# FeatherProto-RJ45-V4_0.net
KiCad netlist of a schematic drawn in EAGLE
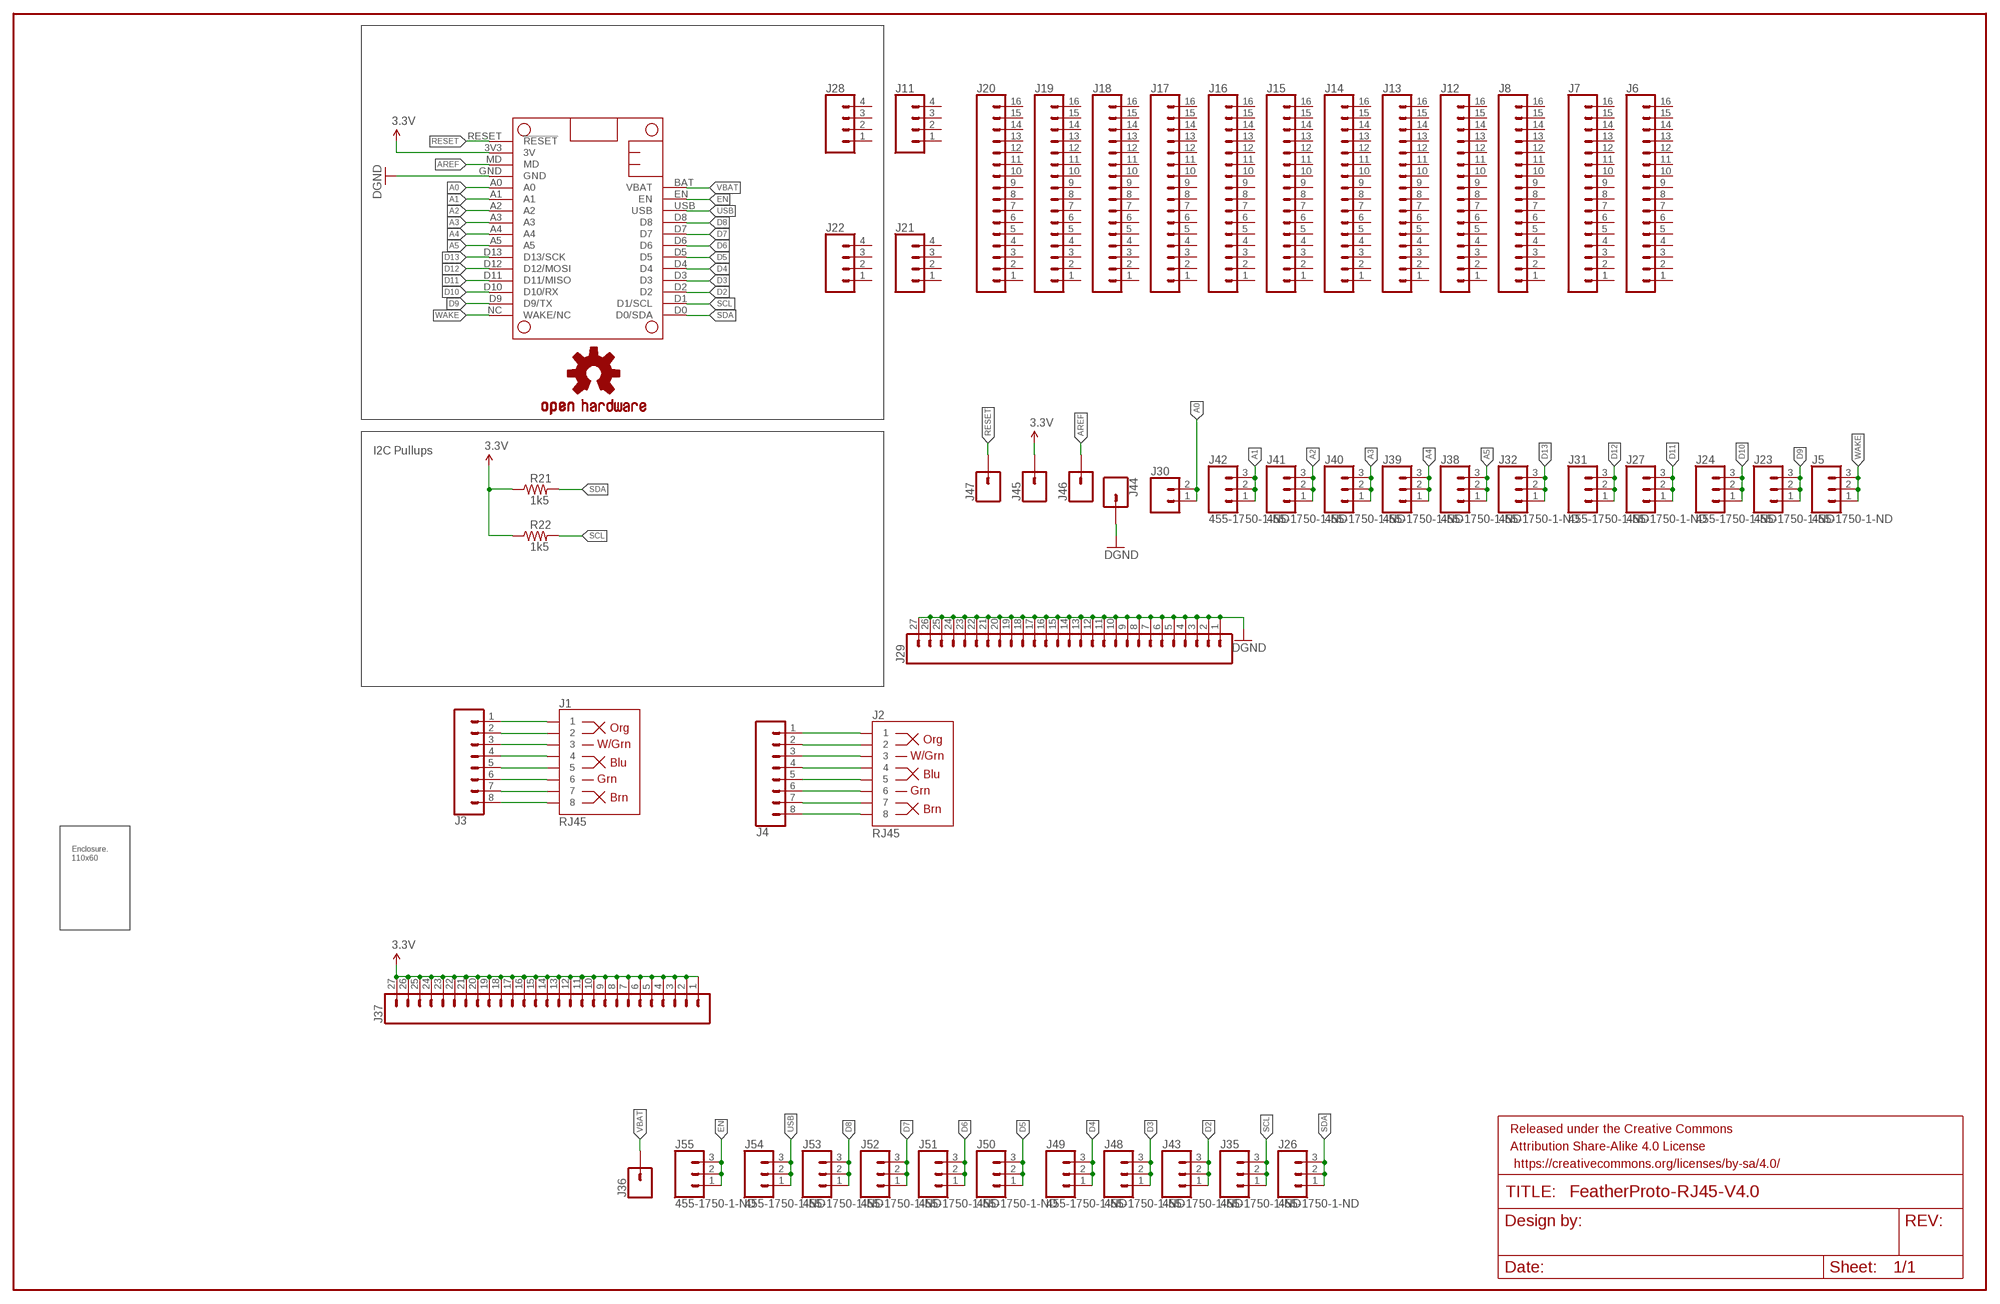
[diagram p0: schematic, sheet 1]

(export (version "E")
  (design (tool "Eeschema 10.0.6"))
  (components
    (comp (ref "FRAME2")
      (value "FRAME-LEDGER")
      (footprint "eagle-import:CREATIVE_COMMONS")
      (libsource (lib "eagle-import") (part "FRAME-LEDGER"))
    )
    (comp (ref "J1")
      (value "RJ45")
      (footprint "eagle-import:RJ45-8")
      (libsource (lib "eagle-import") (part "RJ45-8"))
    )
    (comp (ref "J2")
      (value "RJ45")
      (footprint "eagle-import:RJ45-8")
      (libsource (lib "eagle-import") (part "RJ45-8"))
    )
    (comp (ref "J3")
      (value "CONN_08\"")
      (footprint "eagle-import:1X08")
      (libsource (lib "eagle-import") (part "CONN_08{dblquote}"))
    )
    (comp (ref "J4")
      (value "CONN_08\"")
      (footprint "eagle-import:1X08")
      (libsource (lib "eagle-import") (part "CONN_08{dblquote}"))
    )
    (comp (ref "J5")
      (value "455-1750-1-ND")
      (footprint "eagle-import:1X03")
      (libsource (lib "eagle-import") (part "CONN_03"))
    )
    (comp (ref "J6")
      (value "CONN_161X16_NO_SILK")
      (footprint "eagle-import:1X16_NO_SILK")
      (libsource (lib "eagle-import") (part "CONN_161X16_NO_SILK"))
    )
    (comp (ref "J7")
      (value "CONN_161X16_NO_SILK")
      (footprint "eagle-import:1X16_NO_SILK")
      (libsource (lib "eagle-import") (part "CONN_161X16_NO_SILK"))
    )
    (comp (ref "J8")
      (value "CONN_161X16_NO_SILK")
      (footprint "eagle-import:1X16_NO_SILK")
      (libsource (lib "eagle-import") (part "CONN_161X16_NO_SILK"))
    )
    (comp (ref "J11")
      (value "CONN_041X04_NO_SILK")
      (footprint "eagle-import:1X04_NO_SILK")
      (libsource (lib "eagle-import") (part "CONN_041X04_NO_SILK"))
    )
    (comp (ref "J12")
      (value "CONN_161X16_NO_SILK")
      (footprint "eagle-import:1X16_NO_SILK")
      (libsource (lib "eagle-import") (part "CONN_161X16_NO_SILK"))
    )
    (comp (ref "J13")
      (value "CONN_161X16_NO_SILK")
      (footprint "eagle-import:1X16_NO_SILK")
      (libsource (lib "eagle-import") (part "CONN_161X16_NO_SILK"))
    )
    (comp (ref "J14")
      (value "CONN_161X16_NO_SILK")
      (footprint "eagle-import:1X16_NO_SILK")
      (libsource (lib "eagle-import") (part "CONN_161X16_NO_SILK"))
    )
    (comp (ref "J15")
      (value "CONN_161X16_NO_SILK")
      (footprint "eagle-import:1X16_NO_SILK")
      (libsource (lib "eagle-import") (part "CONN_161X16_NO_SILK"))
    )
    (comp (ref "J16")
      (value "CONN_161X16_NO_SILK")
      (footprint "eagle-import:1X16_NO_SILK")
      (libsource (lib "eagle-import") (part "CONN_161X16_NO_SILK"))
    )
    (comp (ref "J17")
      (value "CONN_161X16_NO_SILK")
      (footprint "eagle-import:1X16_NO_SILK")
      (libsource (lib "eagle-import") (part "CONN_161X16_NO_SILK"))
    )
    (comp (ref "J18")
      (value "CONN_161X16_NO_SILK")
      (footprint "eagle-import:1X16_NO_SILK")
      (libsource (lib "eagle-import") (part "CONN_161X16_NO_SILK"))
    )
    (comp (ref "J19")
      (value "CONN_161X16_NO_SILK")
      (footprint "eagle-import:1X16_NO_SILK")
      (libsource (lib "eagle-import") (part "CONN_161X16_NO_SILK"))
    )
    (comp (ref "J20")
      (value "CONN_161X16_NO_SILK")
      (footprint "eagle-import:1X16_NO_SILK")
      (libsource (lib "eagle-import") (part "CONN_161X16_NO_SILK"))
    )
    (comp (ref "J21")
      (value "CONN_041X04_NO_SILK")
      (footprint "eagle-import:1X04_NO_SILK")
      (libsource (lib "eagle-import") (part "CONN_041X04_NO_SILK"))
    )
    (comp (ref "J22")
      (value "CONN_041X04_NO_SILK")
      (footprint "eagle-import:1X04_NO_SILK")
      (libsource (lib "eagle-import") (part "CONN_041X04_NO_SILK"))
    )
    (comp (ref "J23")
      (value "455-1750-1-ND")
      (footprint "eagle-import:1X03")
      (libsource (lib "eagle-import") (part "CONN_03"))
    )
    (comp (ref "J24")
      (value "455-1750-1-ND")
      (footprint "eagle-import:1X03")
      (libsource (lib "eagle-import") (part "CONN_03"))
    )
    (comp (ref "J26")
      (value "455-1750-1-ND")
      (footprint "eagle-import:1X03")
      (libsource (lib "eagle-import") (part "CONN_03"))
    )
    (comp (ref "J27")
      (value "455-1750-1-ND")
      (footprint "eagle-import:1X03")
      (libsource (lib "eagle-import") (part "CONN_03"))
    )
    (comp (ref "J28")
      (value "CONN_041X04_NO_SILK")
      (footprint "eagle-import:1X04_NO_SILK")
      (libsource (lib "eagle-import") (part "CONN_041X04_NO_SILK"))
    )
    (comp (ref "J29")
      (value "CONN_27")
      (footprint "eagle-import:1X27")
      (libsource (lib "eagle-import") (part "CONN_27"))
    )
    (comp (ref "J30")
      (value "CONN_02")
      (footprint "eagle-import:1X02")
      (libsource (lib "eagle-import") (part "CONN_02"))
    )
    (comp (ref "J31")
      (value "455-1750-1-ND")
      (footprint "eagle-import:1X03")
      (libsource (lib "eagle-import") (part "CONN_03"))
    )
    (comp (ref "J32")
      (value "455-1750-1-ND")
      (footprint "eagle-import:1X03")
      (libsource (lib "eagle-import") (part "CONN_03"))
    )
    (comp (ref "J35")
      (value "455-1750-1-ND")
      (footprint "eagle-import:1X03")
      (libsource (lib "eagle-import") (part "CONN_03"))
    )
    (comp (ref "J36")
      (value "CONN_01PTH_NO_SILK_YES_STOP")
      (footprint "eagle-import:1X01_NO_SILK")
      (libsource (lib "eagle-import") (part "CONN_01PTH_NO_SILK_YES_STOP"))
    )
    (comp (ref "J37")
      (value "CONN_27")
      (footprint "eagle-import:1X27")
      (libsource (lib "eagle-import") (part "CONN_27"))
    )
    (comp (ref "J38")
      (value "455-1750-1-ND")
      (footprint "eagle-import:1X03")
      (libsource (lib "eagle-import") (part "CONN_03"))
    )
    (comp (ref "J39")
      (value "455-1750-1-ND")
      (footprint "eagle-import:1X03")
      (libsource (lib "eagle-import") (part "CONN_03"))
    )
    (comp (ref "J40")
      (value "455-1750-1-ND")
      (footprint "eagle-import:1X03")
      (libsource (lib "eagle-import") (part "CONN_03"))
    )
    (comp (ref "J41")
      (value "455-1750-1-ND")
      (footprint "eagle-import:1X03")
      (libsource (lib "eagle-import") (part "CONN_03"))
    )
    (comp (ref "J42")
      (value "455-1750-1-ND")
      (footprint "eagle-import:1X03")
      (libsource (lib "eagle-import") (part "CONN_03"))
    )
    (comp (ref "J43")
      (value "455-1750-1-ND")
      (footprint "eagle-import:1X03")
      (libsource (lib "eagle-import") (part "CONN_03"))
    )
    (comp (ref "J44")
      (value "CONN_01PTH_NO_SILK_YES_STOP")
      (footprint "eagle-import:1X01_NO_SILK")
      (libsource (lib "eagle-import") (part "CONN_01PTH_NO_SILK_YES_STOP"))
    )
    (comp (ref "J45")
      (value "CONN_01PTH_NO_SILK_YES_STOP")
      (footprint "eagle-import:1X01_NO_SILK")
      (libsource (lib "eagle-import") (part "CONN_01PTH_NO_SILK_YES_STOP"))
    )
    (comp (ref "J46")
      (value "CONN_01PTH_NO_SILK_YES_STOP")
      (footprint "eagle-import:1X01_NO_SILK")
      (libsource (lib "eagle-import") (part "CONN_01PTH_NO_SILK_YES_STOP"))
    )
    (comp (ref "J47")
      (value "CONN_01PTH_NO_SILK_YES_STOP")
      (footprint "eagle-import:1X01_NO_SILK")
      (libsource (lib "eagle-import") (part "CONN_01PTH_NO_SILK_YES_STOP"))
    )
    (comp (ref "J48")
      (value "455-1750-1-ND")
      (footprint "eagle-import:1X03")
      (libsource (lib "eagle-import") (part "CONN_03"))
    )
    (comp (ref "J49")
      (value "455-1750-1-ND")
      (footprint "eagle-import:1X03")
      (libsource (lib "eagle-import") (part "CONN_03"))
    )
    (comp (ref "J50")
      (value "455-1750-1-ND")
      (footprint "eagle-import:1X03")
      (libsource (lib "eagle-import") (part "CONN_03"))
    )
    (comp (ref "J51")
      (value "455-1750-1-ND")
      (footprint "eagle-import:1X03")
      (libsource (lib "eagle-import") (part "CONN_03"))
    )
    (comp (ref "J52")
      (value "455-1750-1-ND")
      (footprint "eagle-import:1X03")
      (libsource (lib "eagle-import") (part "CONN_03"))
    )
    (comp (ref "J53")
      (value "455-1750-1-ND")
      (footprint "eagle-import:1X03")
      (libsource (lib "eagle-import") (part "CONN_03"))
    )
    (comp (ref "J54")
      (value "455-1750-1-ND")
      (footprint "eagle-import:1X03")
      (libsource (lib "eagle-import") (part "CONN_03"))
    )
    (comp (ref "J55")
      (value "455-1750-1-ND")
      (footprint "eagle-import:1X03")
      (libsource (lib "eagle-import") (part "CONN_03"))
    )
    (comp (ref "LOGO1")
      (value "OSHW-LOGOM")
      (footprint "eagle-import:OSHW-LOGO-M")
      (libsource (lib "eagle-import") (part "OSHW-LOGOM"))
    )
    (comp (ref "MS1")
      (value "XENONA")
      (footprint "eagle-import:XENON_BREAKOUT_A")
      (libsource (lib "eagle-import") (part "XENONA"))
    )
    (comp (ref "R21")
      (value "1k5")
      (footprint "eagle-import:0805")
      (libsource (lib "eagle-import") (part "RESISTOR0805"))
    )
    (comp (ref "R22")
      (value "1k5")
      (footprint "eagle-import:0805")
      (libsource (lib "eagle-import") (part "RESISTOR0805"))
    )
    (comp (ref "U$1")
      (value "CAMDENBOSS-ENCLOSURE-110X60MAX")
      (footprint "eagle-import:CAMDENBOSS_ENCLOSRE_110X60_WIDE_EXTENDED_3")
      (libsource (lib "eagle-import") (part "CAMDENBOSS-ENCLOSURE-110X60MAX"))
    )
  )
  (nets
    (net (code "1") (name "3.3V") (class "Default")
      (node (ref "J37") (pin "1") (pinfunction "1_1") (pintype "passive"))
      (node (ref "J37") (pin "10") (pinfunction "10_10") (pintype "passive"))
      (node (ref "J37") (pin "11") (pinfunction "11_11") (pintype "passive"))
      (node (ref "J37") (pin "12") (pinfunction "12_12") (pintype "passive"))
      (node (ref "J37") (pin "13") (pinfunction "13_13") (pintype "passive"))
      (node (ref "J37") (pin "14") (pinfunction "14_14") (pintype "passive"))
      (node (ref "J37") (pin "15") (pinfunction "15_15") (pintype "passive"))
      (node (ref "J37") (pin "16") (pinfunction "16_16") (pintype "passive"))
      (node (ref "J37") (pin "17") (pinfunction "17_17") (pintype "passive"))
      (node (ref "J37") (pin "18") (pinfunction "18_18") (pintype "passive"))
      (node (ref "J37") (pin "19") (pinfunction "19_19") (pintype "passive"))
      (node (ref "J37") (pin "2") (pinfunction "2_2") (pintype "passive"))
      (node (ref "J37") (pin "20") (pinfunction "20_20") (pintype "passive"))
      (node (ref "J37") (pin "21") (pinfunction "21_21") (pintype "passive"))
      (node (ref "J37") (pin "22") (pinfunction "22_22") (pintype "passive"))
      (node (ref "J37") (pin "23") (pinfunction "23_23") (pintype "passive"))
      (node (ref "J37") (pin "24") (pinfunction "24_24") (pintype "passive"))
      (node (ref "J37") (pin "25") (pinfunction "25_25") (pintype "passive"))
      (node (ref "J37") (pin "26") (pinfunction "26_26") (pintype "passive"))
      (node (ref "J37") (pin "27") (pinfunction "27_27") (pintype "passive"))
      (node (ref "J37") (pin "3") (pinfunction "3_3") (pintype "passive"))
      (node (ref "J37") (pin "4") (pinfunction "4_4") (pintype "passive"))
      (node (ref "J37") (pin "5") (pinfunction "5_5") (pintype "passive"))
      (node (ref "J37") (pin "6") (pinfunction "6_6") (pintype "passive"))
      (node (ref "J37") (pin "7") (pinfunction "7_7") (pintype "passive"))
      (node (ref "J37") (pin "8") (pinfunction "8_8") (pintype "passive"))
      (node (ref "J37") (pin "9") (pinfunction "9_9") (pintype "passive"))
      (node (ref "J45") (pin "1") (pinfunction "1_1") (pintype "passive"))
      (node (ref "MS1") (pin "3V3") (pinfunction "3V_3V3") (pintype "power_in"))
      (node (ref "R21") (pin "1") (pinfunction "1_1") (pintype "passive"))
      (node (ref "R22") (pin "1") (pinfunction "1_1") (pintype "passive"))
    )
    (net (code "2") (name "A0") (class "Default")
      (node (ref "J30") (pin "1") (pinfunction "1_1") (pintype "passive"))
      (node (ref "J30") (pin "2") (pinfunction "2_2") (pintype "passive"))
      (node (ref "MS1") (pin "A0") (pinfunction "A0_A0") (pintype "bidirectional"))
    )
    (net (code "3") (name "A1") (class "Default")
      (node (ref "J42") (pin "1") (pinfunction "1_1") (pintype "passive"))
      (node (ref "J42") (pin "2") (pinfunction "2_2") (pintype "passive"))
      (node (ref "J42") (pin "3") (pinfunction "3_3") (pintype "passive"))
      (node (ref "MS1") (pin "A1") (pinfunction "A1_A1") (pintype "bidirectional"))
    )
    (net (code "4") (name "A2") (class "Default")
      (node (ref "J41") (pin "1") (pinfunction "1_1") (pintype "passive"))
      (node (ref "J41") (pin "2") (pinfunction "2_2") (pintype "passive"))
      (node (ref "J41") (pin "3") (pinfunction "3_3") (pintype "passive"))
      (node (ref "MS1") (pin "A2") (pinfunction "A2_A2") (pintype "bidirectional"))
    )
    (net (code "5") (name "A3") (class "Default")
      (node (ref "J40") (pin "1") (pinfunction "1_1") (pintype "passive"))
      (node (ref "J40") (pin "2") (pinfunction "2_2") (pintype "passive"))
      (node (ref "J40") (pin "3") (pinfunction "3_3") (pintype "passive"))
      (node (ref "MS1") (pin "A3") (pinfunction "A3_A3") (pintype "bidirectional"))
    )
    (net (code "6") (name "A4") (class "Default")
      (node (ref "J39") (pin "1") (pinfunction "1_1") (pintype "passive"))
      (node (ref "J39") (pin "2") (pinfunction "2_2") (pintype "passive"))
      (node (ref "J39") (pin "3") (pinfunction "3_3") (pintype "passive"))
      (node (ref "MS1") (pin "A4") (pinfunction "A4_A4") (pintype "bidirectional"))
    )
    (net (code "7") (name "A5") (class "Default")
      (node (ref "J38") (pin "1") (pinfunction "1_1") (pintype "passive"))
      (node (ref "J38") (pin "2") (pinfunction "2_2") (pintype "passive"))
      (node (ref "J38") (pin "3") (pinfunction "3_3") (pintype "passive"))
      (node (ref "MS1") (pin "A5") (pinfunction "A5_A5") (pintype "bidirectional"))
    )
    (net (code "8") (name "AREF") (class "Default")
      (node (ref "J46") (pin "1") (pinfunction "1_1") (pintype "passive"))
      (node (ref "MS1") (pin "MD") (pinfunction "MD_MD") (pintype "passive"))
    )
    (net (code "9") (name "D2") (class "Default")
      (node (ref "J43") (pin "1") (pinfunction "1_1") (pintype "passive"))
      (node (ref "J43") (pin "2") (pinfunction "2_2") (pintype "passive"))
      (node (ref "J43") (pin "3") (pinfunction "3_3") (pintype "passive"))
      (node (ref "MS1") (pin "D2") (pinfunction "D2_D2") (pintype "bidirectional"))
    )
    (net (code "10") (name "D3") (class "Default")
      (node (ref "J48") (pin "1") (pinfunction "1_1") (pintype "passive"))
      (node (ref "J48") (pin "2") (pinfunction "2_2") (pintype "passive"))
      (node (ref "J48") (pin "3") (pinfunction "3_3") (pintype "passive"))
      (node (ref "MS1") (pin "D3") (pinfunction "D3_D3") (pintype "bidirectional"))
    )
    (net (code "11") (name "D4") (class "Default")
      (node (ref "J49") (pin "1") (pinfunction "1_1") (pintype "passive"))
      (node (ref "J49") (pin "2") (pinfunction "2_2") (pintype "passive"))
      (node (ref "J49") (pin "3") (pinfunction "3_3") (pintype "passive"))
      (node (ref "MS1") (pin "D4") (pinfunction "D4_D4") (pintype "bidirectional"))
    )
    (net (code "12") (name "D5") (class "Default")
      (node (ref "J50") (pin "1") (pinfunction "1_1") (pintype "passive"))
      (node (ref "J50") (pin "2") (pinfunction "2_2") (pintype "passive"))
      (node (ref "J50") (pin "3") (pinfunction "3_3") (pintype "passive"))
      (node (ref "MS1") (pin "D5") (pinfunction "D5_D5") (pintype "bidirectional"))
    )
    (net (code "13") (name "D6") (class "Default")
      (node (ref "J51") (pin "1") (pinfunction "1_1") (pintype "passive"))
      (node (ref "J51") (pin "2") (pinfunction "2_2") (pintype "passive"))
      (node (ref "J51") (pin "3") (pinfunction "3_3") (pintype "passive"))
      (node (ref "MS1") (pin "D6") (pinfunction "D6_D6") (pintype "bidirectional"))
    )
    (net (code "14") (name "D7") (class "Default")
      (node (ref "J52") (pin "1") (pinfunction "1_1") (pintype "passive"))
      (node (ref "J52") (pin "2") (pinfunction "2_2") (pintype "passive"))
      (node (ref "J52") (pin "3") (pinfunction "3_3") (pintype "passive"))
      (node (ref "MS1") (pin "D7") (pinfunction "D7_D7") (pintype "bidirectional"))
    )
    (net (code "15") (name "D8") (class "Default")
      (node (ref "J53") (pin "1") (pinfunction "1_1") (pintype "passive"))
      (node (ref "J53") (pin "2") (pinfunction "2_2") (pintype "passive"))
      (node (ref "J53") (pin "3") (pinfunction "3_3") (pintype "passive"))
      (node (ref "MS1") (pin "D8") (pinfunction "D8_D8") (pintype "bidirectional"))
    )
    (net (code "16") (name "D9") (class "Default")
      (node (ref "J23") (pin "1") (pinfunction "1_1") (pintype "passive"))
      (node (ref "J23") (pin "2") (pinfunction "2_2") (pintype "passive"))
      (node (ref "J23") (pin "3") (pinfunction "3_3") (pintype "passive"))
      (node (ref "MS1") (pin "D9") (pinfunction "D9/TX_D9") (pintype "bidirectional"))
    )
    (net (code "17") (name "D10") (class "Default")
      (node (ref "J24") (pin "1") (pinfunction "1_1") (pintype "passive"))
      (node (ref "J24") (pin "2") (pinfunction "2_2") (pintype "passive"))
      (node (ref "J24") (pin "3") (pinfunction "3_3") (pintype "passive"))
      (node (ref "MS1") (pin "D10") (pinfunction "D10/RX_D10") (pintype "bidirectional"))
    )
    (net (code "18") (name "D11") (class "Default")
      (node (ref "J27") (pin "1") (pinfunction "1_1") (pintype "passive"))
      (node (ref "J27") (pin "2") (pinfunction "2_2") (pintype "passive"))
      (node (ref "J27") (pin "3") (pinfunction "3_3") (pintype "passive"))
      (node (ref "MS1") (pin "D11") (pinfunction "D11/MISO_D11") (pintype "bidirectional"))
    )
    (net (code "19") (name "D12") (class "Default")
      (node (ref "J31") (pin "1") (pinfunction "1_1") (pintype "passive"))
      (node (ref "J31") (pin "2") (pinfunction "2_2") (pintype "passive"))
      (node (ref "J31") (pin "3") (pinfunction "3_3") (pintype "passive"))
      (node (ref "MS1") (pin "D12") (pinfunction "D12/MOSI_D12") (pintype "bidirectional"))
    )
    (net (code "20") (name "D13") (class "Default")
      (node (ref "J32") (pin "1") (pinfunction "1_1") (pintype "passive"))
      (node (ref "J32") (pin "2") (pinfunction "2_2") (pintype "passive"))
      (node (ref "J32") (pin "3") (pinfunction "3_3") (pintype "passive"))
      (node (ref "MS1") (pin "D13") (pinfunction "D13/SCK_D13") (pintype "bidirectional"))
    )
    (net (code "21") (name "DGND") (class "Default")
      (node (ref "J29") (pin "1") (pinfunction "1_1") (pintype "passive"))
      (node (ref "J29") (pin "10") (pinfunction "10_10") (pintype "passive"))
      (node (ref "J29") (pin "11") (pinfunction "11_11") (pintype "passive"))
      (node (ref "J29") (pin "12") (pinfunction "12_12") (pintype "passive"))
      (node (ref "J29") (pin "13") (pinfunction "13_13") (pintype "passive"))
      (node (ref "J29") (pin "14") (pinfunction "14_14") (pintype "passive"))
      (node (ref "J29") (pin "15") (pinfunction "15_15") (pintype "passive"))
      (node (ref "J29") (pin "16") (pinfunction "16_16") (pintype "passive"))
      (node (ref "J29") (pin "17") (pinfunction "17_17") (pintype "passive"))
      (node (ref "J29") (pin "18") (pinfunction "18_18") (pintype "passive"))
      (node (ref "J29") (pin "19") (pinfunction "19_19") (pintype "passive"))
      (node (ref "J29") (pin "2") (pinfunction "2_2") (pintype "passive"))
      (node (ref "J29") (pin "20") (pinfunction "20_20") (pintype "passive"))
      (node (ref "J29") (pin "21") (pinfunction "21_21") (pintype "passive"))
      (node (ref "J29") (pin "22") (pinfunction "22_22") (pintype "passive"))
      (node (ref "J29") (pin "23") (pinfunction "23_23") (pintype "passive"))
      (node (ref "J29") (pin "24") (pinfunction "24_24") (pintype "passive"))
      (node (ref "J29") (pin "25") (pinfunction "25_25") (pintype "passive"))
      (node (ref "J29") (pin "26") (pinfunction "26_26") (pintype "passive"))
      (node (ref "J29") (pin "27") (pinfunction "27_27") (pintype "passive"))
      (node (ref "J29") (pin "3") (pinfunction "3_3") (pintype "passive"))
      (node (ref "J29") (pin "4") (pinfunction "4_4") (pintype "passive"))
      (node (ref "J29") (pin "5") (pinfunction "5_5") (pintype "passive"))
      (node (ref "J29") (pin "6") (pinfunction "6_6") (pintype "passive"))
      (node (ref "J29") (pin "7") (pinfunction "7_7") (pintype "passive"))
      (node (ref "J29") (pin "8") (pinfunction "8_8") (pintype "passive"))
      (node (ref "J29") (pin "9") (pinfunction "9_9") (pintype "passive"))
      (node (ref "J44") (pin "1") (pinfunction "1_1") (pintype "passive"))
      (node (ref "MS1") (pin "GND") (pinfunction "GND_GND") (pintype "power_in"))
    )
    (net (code "22") (name "EN") (class "Default")
      (node (ref "J55") (pin "1") (pinfunction "1_1") (pintype "passive"))
      (node (ref "J55") (pin "2") (pinfunction "2_2") (pintype "passive"))
      (node (ref "J55") (pin "3") (pinfunction "3_3") (pintype "passive"))
      (node (ref "MS1") (pin "EN") (pinfunction "EN_EN") (pintype "passive"))
    )
    (net (code "23") (name "Net-(J1-Pad1)") (class "Default")
      (node (ref "J1") (pin "1") (pinfunction "1_1") (pintype "bidirectional"))
      (node (ref "J3") (pin "1") (pinfunction "1_1") (pintype "passive"))
    )
    (net (code "24") (name "Net-(J1-Pad2)") (class "Default")
      (node (ref "J1") (pin "2") (pinfunction "2_2") (pintype "bidirectional"))
      (node (ref "J3") (pin "2") (pinfunction "2_2") (pintype "passive"))
    )
    (net (code "25") (name "Net-(J1-Pad3)") (class "Default")
      (node (ref "J1") (pin "3") (pinfunction "3_3") (pintype "bidirectional"))
      (node (ref "J3") (pin "3") (pinfunction "3_3") (pintype "passive"))
    )
    (net (code "26") (name "Net-(J1-Pad4)") (class "Default")
      (node (ref "J1") (pin "4") (pinfunction "4_4") (pintype "bidirectional"))
      (node (ref "J3") (pin "4") (pinfunction "4_4") (pintype "passive"))
    )
    (net (code "27") (name "Net-(J1-Pad5)") (class "Default")
      (node (ref "J1") (pin "5") (pinfunction "5_5") (pintype "bidirectional"))
      (node (ref "J3") (pin "5") (pinfunction "5_5") (pintype "passive"))
    )
    (net (code "28") (name "Net-(J1-Pad6)") (class "Default")
      (node (ref "J1") (pin "6") (pinfunction "6_6") (pintype "bidirectional"))
      (node (ref "J3") (pin "6") (pinfunction "6_6") (pintype "passive"))
    )
    (net (code "29") (name "Net-(J1-Pad7)") (class "Default")
      (node (ref "J1") (pin "7") (pinfunction "7_7") (pintype "bidirectional"))
      (node (ref "J3") (pin "7") (pinfunction "7_7") (pintype "passive"))
    )
    (net (code "30") (name "Net-(J1-Pad8)") (class "Default")
      (node (ref "J1") (pin "8") (pinfunction "8_8") (pintype "bidirectional"))
      (node (ref "J3") (pin "8") (pinfunction "8_8") (pintype "passive"))
    )
    (net (code "31") (name "Net-(J2-Pad1)") (class "Default")
      (node (ref "J2") (pin "1") (pinfunction "1_1") (pintype "bidirectional"))
      (node (ref "J4") (pin "1") (pinfunction "1_1") (pintype "passive"))
    )
    (net (code "32") (name "Net-(J2-Pad2)") (class "Default")
      (node (ref "J2") (pin "2") (pinfunction "2_2") (pintype "bidirectional"))
      (node (ref "J4") (pin "2") (pinfunction "2_2") (pintype "passive"))
    )
    (net (code "33") (name "Net-(J2-Pad3)") (class "Default")
      (node (ref "J2") (pin "3") (pinfunction "3_3") (pintype "bidirectional"))
      (node (ref "J4") (pin "3") (pinfunction "3_3") (pintype "passive"))
    )
    (net (code "34") (name "Net-(J2-Pad4)") (class "Default")
      (node (ref "J2") (pin "4") (pinfunction "4_4") (pintype "bidirectional"))
      (node (ref "J4") (pin "4") (pinfunction "4_4") (pintype "passive"))
    )
    (net (code "35") (name "Net-(J2-Pad5)") (class "Default")
      (node (ref "J2") (pin "5") (pinfunction "5_5") (pintype "bidirectional"))
      (node (ref "J4") (pin "5") (pinfunction "5_5") (pintype "passive"))
    )
    (net (code "36") (name "Net-(J2-Pad6)") (class "Default")
      (node (ref "J2") (pin "6") (pinfunction "6_6") (pintype "bidirectional"))
      (node (ref "J4") (pin "6") (pinfunction "6_6") (pintype "passive"))
    )
    (net (code "37") (name "Net-(J2-Pad7)") (class "Default")
      (node (ref "J2") (pin "7") (pinfunction "7_7") (pintype "bidirectional"))
      (node (ref "J4") (pin "7") (pinfunction "7_7") (pintype "passive"))
    )
    (net (code "38") (name "Net-(J2-Pad8)") (class "Default")
      (node (ref "J2") (pin "8") (pinfunction "8_8") (pintype "bidirectional"))
      (node (ref "J4") (pin "8") (pinfunction "8_8") (pintype "passive"))
    )
    (net (code "39") (name "RESET") (class "Default")
      (node (ref "J47") (pin "1") (pinfunction "1_1") (pintype "passive"))
      (node (ref "MS1") (pin "RESET") (pinfunction "~{RESET}_RESET") (pintype "input"))
    )
    (net (code "40") (name "SCL") (class "Default")
      (node (ref "J35") (pin "1") (pinfunction "1_1") (pintype "passive"))
      (node (ref "J35") (pin "2") (pinfunction "2_2") (pintype "passive"))
      (node (ref "J35") (pin "3") (pinfunction "3_3") (pintype "passive"))
      (node (ref "MS1") (pin "D1") (pinfunction "D1/SCL_D1") (pintype "bidirectional"))
      (node (ref "R22") (pin "2") (pinfunction "2_2") (pintype "passive"))
    )
    (net (code "41") (name "SDA") (class "Default")
      (node (ref "J26") (pin "1") (pinfunction "1_1") (pintype "passive"))
      (node (ref "J26") (pin "2") (pinfunction "2_2") (pintype "passive"))
      (node (ref "J26") (pin "3") (pinfunction "3_3") (pintype "passive"))
      (node (ref "MS1") (pin "D0") (pinfunction "D0/SDA_D0") (pintype "bidirectional"))
      (node (ref "R21") (pin "2") (pinfunction "2_2") (pintype "passive"))
    )
    (net (code "42") (name "USB") (class "Default")
      (node (ref "J54") (pin "1") (pinfunction "1_1") (pintype "passive"))
      (node (ref "J54") (pin "2") (pinfunction "2_2") (pintype "passive"))
      (node (ref "J54") (pin "3") (pinfunction "3_3") (pintype "passive"))
      (node (ref "MS1") (pin "USB") (pinfunction "USB_USB") (pintype "power_in"))
    )
    (net (code "43") (name "VBAT") (class "Default")
      (node (ref "J36") (pin "1") (pinfunction "1_1") (pintype "passive"))
      (node (ref "MS1") (pin "BAT") (pinfunction "VBAT_BAT") (pintype "power_in"))
    )
    (net (code "44") (name "WAKE") (class "Default")
      (node (ref "J5") (pin "1") (pinfunction "1_1") (pintype "passive"))
      (node (ref "J5") (pin "2") (pinfunction "2_2") (pintype "passive"))
      (node (ref "J5") (pin "3") (pinfunction "3_3") (pintype "passive"))
      (node (ref "MS1") (pin "NC") (pinfunction "WAKE/NC_NC") (pintype "passive"))
    )
    (net (code "45") (name "unconnected-(J6-Pad1)") (class "Default")
      (node (ref "J6") (pin "1") (pinfunction "1_1") (pintype "passive"))
    )
    (net (code "46") (name "unconnected-(J6-Pad2)") (class "Default")
      (node (ref "J6") (pin "2") (pinfunction "2_2") (pintype "passive"))
    )
    (net (code "47") (name "unconnected-(J6-Pad3)") (class "Default")
      (node (ref "J6") (pin "3") (pinfunction "3_3") (pintype "passive"))
    )
    (net (code "48") (name "unconnected-(J6-Pad4)") (class "Default")
      (node (ref "J6") (pin "4") (pinfunction "4_4") (pintype "passive"))
    )
    (net (code "49") (name "unconnected-(J6-Pad5)") (class "Default")
      (node (ref "J6") (pin "5") (pinfunction "5_5") (pintype "passive"))
    )
    (net (code "50") (name "unconnected-(J6-Pad6)") (class "Default")
      (node (ref "J6") (pin "6") (pinfunction "6_6") (pintype "passive"))
    )
    (net (code "51") (name "unconnected-(J6-Pad7)") (class "Default")
      (node (ref "J6") (pin "7") (pinfunction "7_7") (pintype "passive"))
    )
    (net (code "52") (name "unconnected-(J6-Pad8)") (class "Default")
      (node (ref "J6") (pin "8") (pinfunction "8_8") (pintype "passive"))
    )
    (net (code "53") (name "unconnected-(J6-Pad9)") (class "Default")
      (node (ref "J6") (pin "9") (pinfunction "9_9") (pintype "passive"))
    )
    (net (code "54") (name "unconnected-(J6-Pad10)") (class "Default")
      (node (ref "J6") (pin "10") (pinfunction "10_10") (pintype "passive"))
    )
    (net (code "55") (name "unconnected-(J6-Pad11)") (class "Default")
      (node (ref "J6") (pin "11") (pinfunction "11_11") (pintype "passive"))
    )
    (net (code "56") (name "unconnected-(J6-Pad12)") (class "Default")
      (node (ref "J6") (pin "12") (pinfunction "12_12") (pintype "passive"))
    )
    (net (code "57") (name "unconnected-(J6-Pad13)") (class "Default")
      (node (ref "J6") (pin "13") (pinfunction "13_13") (pintype "passive"))
    )
    (net (code "58") (name "unconnected-(J6-Pad14)") (class "Default")
      (node (ref "J6") (pin "14") (pinfunction "14_14") (pintype "passive"))
    )
    (net (code "59") (name "unconnected-(J6-Pad15)") (class "Default")
      (node (ref "J6") (pin "15") (pinfunction "15_15") (pintype "passive"))
    )
    (net (code "60") (name "unconnected-(J6-Pad16)") (class "Default")
      (node (ref "J6") (pin "16") (pinfunction "16_16") (pintype "passive"))
    )
    (net (code "61") (name "unconnected-(J7-Pad1)") (class "Default")
      (node (ref "J7") (pin "1") (pinfunction "1_1") (pintype "passive"))
    )
    (net (code "62") (name "unconnected-(J7-Pad2)") (class "Default")
      (node (ref "J7") (pin "2") (pinfunction "2_2") (pintype "passive"))
    )
    (net (code "63") (name "unconnected-(J7-Pad3)") (class "Default")
      (node (ref "J7") (pin "3") (pinfunction "3_3") (pintype "passive"))
    )
    (net (code "64") (name "unconnected-(J7-Pad4)") (class "Default")
      (node (ref "J7") (pin "4") (pinfunction "4_4") (pintype "passive"))
    )
    (net (code "65") (name "unconnected-(J7-Pad5)") (class "Default")
      (node (ref "J7") (pin "5") (pinfunction "5_5") (pintype "passive"))
    )
    (net (code "66") (name "unconnected-(J7-Pad6)") (class "Default")
      (node (ref "J7") (pin "6") (pinfunction "6_6") (pintype "passive"))
    )
    (net (code "67") (name "unconnected-(J7-Pad7)") (class "Default")
      (node (ref "J7") (pin "7") (pinfunction "7_7") (pintype "passive"))
    )
    (net (code "68") (name "unconnected-(J7-Pad8)") (class "Default")
      (node (ref "J7") (pin "8") (pinfunction "8_8") (pintype "passive"))
    )
    (net (code "69") (name "unconnected-(J7-Pad9)") (class "Default")
      (node (ref "J7") (pin "9") (pinfunction "9_9") (pintype "passive"))
    )
    (net (code "70") (name "unconnected-(J7-Pad10)") (class "Default")
      (node (ref "J7") (pin "10") (pinfunction "10_10") (pintype "passive"))
    )
    (net (code "71") (name "unconnected-(J7-Pad11)") (class "Default")
      (node (ref "J7") (pin "11") (pinfunction "11_11") (pintype "passive"))
    )
    (net (code "72") (name "unconnected-(J7-Pad12)") (class "Default")
      (node (ref "J7") (pin "12") (pinfunction "12_12") (pintype "passive"))
    )
    (net (code "73") (name "unconnected-(J7-Pad13)") (class "Default")
      (node (ref "J7") (pin "13") (pinfunction "13_13") (pintype "passive"))
    )
    (net (code "74") (name "unconnected-(J7-Pad14)") (class "Default")
      (node (ref "J7") (pin "14") (pinfunction "14_14") (pintype "passive"))
    )
    (net (code "75") (name "unconnected-(J7-Pad15)") (class "Default")
      (node (ref "J7") (pin "15") (pinfunction "15_15") (pintype "passive"))
    )
    (net (code "76") (name "unconnected-(J7-Pad16)") (class "Default")
      (node (ref "J7") (pin "16") (pinfunction "16_16") (pintype "passive"))
    )
    (net (code "77") (name "unconnected-(J8-Pad1)") (class "Default")
      (node (ref "J8") (pin "1") (pinfunction "1_1") (pintype "passive"))
    )
    (net (code "78") (name "unconnected-(J8-Pad2)") (class "Default")
      (node (ref "J8") (pin "2") (pinfunction "2_2") (pintype "passive"))
    )
    (net (code "79") (name "unconnected-(J8-Pad3)") (class "Default")
      (node (ref "J8") (pin "3") (pinfunction "3_3") (pintype "passive"))
    )
    (net (code "80") (name "unconnected-(J8-Pad4)") (class "Default")
      (node (ref "J8") (pin "4") (pinfunction "4_4") (pintype "passive"))
    )
    (net (code "81") (name "unconnected-(J8-Pad5)") (class "Default")
      (node (ref "J8") (pin "5") (pinfunction "5_5") (pintype "passive"))
    )
    (net (code "82") (name "unconnected-(J8-Pad6)") (class "Default")
      (node (ref "J8") (pin "6") (pinfunction "6_6") (pintype "passive"))
    )
    (net (code "83") (name "unconnected-(J8-Pad7)") (class "Default")
      (node (ref "J8") (pin "7") (pinfunction "7_7") (pintype "passive"))
    )
    (net (code "84") (name "unconnected-(J8-Pad8)") (class "Default")
      (node (ref "J8") (pin "8") (pinfunction "8_8") (pintype "passive"))
    )
    (net (code "85") (name "unconnected-(J8-Pad9)") (class "Default")
      (node (ref "J8") (pin "9") (pinfunction "9_9") (pintype "passive"))
    )
    (net (code "86") (name "unconnected-(J8-Pad10)") (class "Default")
      (node (ref "J8") (pin "10") (pinfunction "10_10") (pintype "passive"))
    )
    (net (code "87") (name "unconnected-(J8-Pad11)") (class "Default")
      (node (ref "J8") (pin "11") (pinfunction "11_11") (pintype "passive"))
    )
    (net (code "88") (name "unconnected-(J8-Pad12)") (class "Default")
      (node (ref "J8") (pin "12") (pinfunction "12_12") (pintype "passive"))
    )
    (net (code "89") (name "unconnected-(J8-Pad13)") (class "Default")
      (node (ref "J8") (pin "13") (pinfunction "13_13") (pintype "passive"))
    )
    (net (code "90") (name "unconnected-(J8-Pad14)") (class "Default")
      (node (ref "J8") (pin "14") (pinfunction "14_14") (pintype "passive"))
    )
    (net (code "91") (name "unconnected-(J8-Pad15)") (class "Default")
      (node (ref "J8") (pin "15") (pinfunction "15_15") (pintype "passive"))
    )
    (net (code "92") (name "unconnected-(J8-Pad16)") (class "Default")
      (node (ref "J8") (pin "16") (pinfunction "16_16") (pintype "passive"))
    )
    (net (code "93") (name "unconnected-(J11-Pad1)") (class "Default")
      (node (ref "J11") (pin "1") (pinfunction "1_1") (pintype "passive"))
    )
    (net (code "94") (name "unconnected-(J11-Pad2)") (class "Default")
      (node (ref "J11") (pin "2") (pinfunction "2_2") (pintype "passive"))
    )
    (net (code "95") (name "unconnected-(J11-Pad3)") (class "Default")
      (node (ref "J11") (pin "3") (pinfunction "3_3") (pintype "passive"))
    )
    (net (code "96") (name "unconnected-(J11-Pad4)") (class "Default")
      (node (ref "J11") (pin "4") (pinfunction "4_4") (pintype "passive"))
    )
    (net (code "97") (name "unconnected-(J12-Pad1)") (class "Default")
      (node (ref "J12") (pin "1") (pinfunction "1_1") (pintype "passive"))
    )
    (net (code "98") (name "unconnected-(J12-Pad2)") (class "Default")
      (node (ref "J12") (pin "2") (pinfunction "2_2") (pintype "passive"))
    )
    (net (code "99") (name "unconnected-(J12-Pad3)") (class "Default")
      (node (ref "J12") (pin "3") (pinfunction "3_3") (pintype "passive"))
    )
    (net (code "100") (name "unconnected-(J12-Pad4)") (class "Default")
      (node (ref "J12") (pin "4") (pinfunction "4_4") (pintype "passive"))
    )
    (net (code "101") (name "unconnected-(J12-Pad5)") (class "Default")
      (node (ref "J12") (pin "5") (pinfunction "5_5") (pintype "passive"))
    )
    (net (code "102") (name "unconnected-(J12-Pad6)") (class "Default")
      (node (ref "J12") (pin "6") (pinfunction "6_6") (pintype "passive"))
    )
    (net (code "103") (name "unconnected-(J12-Pad7)") (class "Default")
      (node (ref "J12") (pin "7") (pinfunction "7_7") (pintype "passive"))
    )
    (net (code "104") (name "unconnected-(J12-Pad8)") (class "Default")
      (node (ref "J12") (pin "8") (pinfunction "8_8") (pintype "passive"))
    )
    (net (code "105") (name "unconnected-(J12-Pad9)") (class "Default")
      (node (ref "J12") (pin "9") (pinfunction "9_9") (pintype "passive"))
    )
    (net (code "106") (name "unconnected-(J12-Pad10)") (class "Default")
      (node (ref "J12") (pin "10") (pinfunction "10_10") (pintype "passive"))
    )
    (net (code "107") (name "unconnected-(J12-Pad11)") (class "Default")
      (node (ref "J12") (pin "11") (pinfunction "11_11") (pintype "passive"))
    )
    (net (code "108") (name "unconnected-(J12-Pad12)") (class "Default")
      (node (ref "J12") (pin "12") (pinfunction "12_12") (pintype "passive"))
    )
    (net (code "109") (name "unconnected-(J12-Pad13)") (class "Default")
      (node (ref "J12") (pin "13") (pinfunction "13_13") (pintype "passive"))
    )
    (net (code "110") (name "unconnected-(J12-Pad14)") (class "Default")
      (node (ref "J12") (pin "14") (pinfunction "14_14") (pintype "passive"))
    )
    (net (code "111") (name "unconnected-(J12-Pad15)") (class "Default")
      (node (ref "J12") (pin "15") (pinfunction "15_15") (pintype "passive"))
    )
    (net (code "112") (name "unconnected-(J12-Pad16)") (class "Default")
      (node (ref "J12") (pin "16") (pinfunction "16_16") (pintype "passive"))
    )
    (net (code "113") (name "unconnected-(J13-Pad1)") (class "Default")
      (node (ref "J13") (pin "1") (pinfunction "1_1") (pintype "passive"))
    )
    (net (code "114") (name "unconnected-(J13-Pad2)") (class "Default")
      (node (ref "J13") (pin "2") (pinfunction "2_2") (pintype "passive"))
    )
    (net (code "115") (name "unconnected-(J13-Pad3)") (class "Default")
      (node (ref "J13") (pin "3") (pinfunction "3_3") (pintype "passive"))
    )
    (net (code "116") (name "unconnected-(J13-Pad4)") (class "Default")
      (node (ref "J13") (pin "4") (pinfunction "4_4") (pintype "passive"))
    )
    (net (code "117") (name "unconnected-(J13-Pad5)") (class "Default")
      (node (ref "J13") (pin "5") (pinfunction "5_5") (pintype "passive"))
    )
    (net (code "118") (name "unconnected-(J13-Pad6)") (class "Default")
      (node (ref "J13") (pin "6") (pinfunction "6_6") (pintype "passive"))
    )
    (net (code "119") (name "unconnected-(J13-Pad7)") (class "Default")
      (node (ref "J13") (pin "7") (pinfunction "7_7") (pintype "passive"))
    )
    (net (code "120") (name "unconnected-(J13-Pad8)") (class "Default")
      (node (ref "J13") (pin "8") (pinfunction "8_8") (pintype "passive"))
    )
    (net (code "121") (name "unconnected-(J13-Pad9)") (class "Default")
      (node (ref "J13") (pin "9") (pinfunction "9_9") (pintype "passive"))
    )
    (net (code "122") (name "unconnected-(J13-Pad10)") (class "Default")
      (node (ref "J13") (pin "10") (pinfunction "10_10") (pintype "passive"))
    )
    (net (code "123") (name "unconnected-(J13-Pad11)") (class "Default")
      (node (ref "J13") (pin "11") (pinfunction "11_11") (pintype "passive"))
    )
    (net (code "124") (name "unconnected-(J13-Pad12)") (class "Default")
      (node (ref "J13") (pin "12") (pinfunction "12_12") (pintype "passive"))
    )
    (net (code "125") (name "unconnected-(J13-Pad13)") (class "Default")
      (node (ref "J13") (pin "13") (pinfunction "13_13") (pintype "passive"))
    )
    (net (code "126") (name "unconnected-(J13-Pad14)") (class "Default")
      (node (ref "J13") (pin "14") (pinfunction "14_14") (pintype "passive"))
    )
    (net (code "127") (name "unconnected-(J13-Pad15)") (class "Default")
      (node (ref "J13") (pin "15") (pinfunction "15_15") (pintype "passive"))
    )
    (net (code "128") (name "unconnected-(J13-Pad16)") (class "Default")
      (node (ref "J13") (pin "16") (pinfunction "16_16") (pintype "passive"))
    )
    (net (code "129") (name "unconnected-(J14-Pad1)") (class "Default")
      (node (ref "J14") (pin "1") (pinfunction "1_1") (pintype "passive"))
    )
    (net (code "130") (name "unconnected-(J14-Pad2)") (class "Default")
      (node (ref "J14") (pin "2") (pinfunction "2_2") (pintype "passive"))
    )
    (net (code "131") (name "unconnected-(J14-Pad3)") (class "Default")
      (node (ref "J14") (pin "3") (pinfunction "3_3") (pintype "passive"))
    )
    (net (code "132") (name "unconnected-(J14-Pad4)") (class "Default")
      (node (ref "J14") (pin "4") (pinfunction "4_4") (pintype "passive"))
    )
    (net (code "133") (name "unconnected-(J14-Pad5)") (class "Default")
      (node (ref "J14") (pin "5") (pinfunction "5_5") (pintype "passive"))
    )
    (net (code "134") (name "unconnected-(J14-Pad6)") (class "Default")
      (node (ref "J14") (pin "6") (pinfunction "6_6") (pintype "passive"))
    )
    (net (code "135") (name "unconnected-(J14-Pad7)") (class "Default")
      (node (ref "J14") (pin "7") (pinfunction "7_7") (pintype "passive"))
    )
    (net (code "136") (name "unconnected-(J14-Pad8)") (class "Default")
      (node (ref "J14") (pin "8") (pinfunction "8_8") (pintype "passive"))
    )
    (net (code "137") (name "unconnected-(J14-Pad9)") (class "Default")
      (node (ref "J14") (pin "9") (pinfunction "9_9") (pintype "passive"))
    )
    (net (code "138") (name "unconnected-(J14-Pad10)") (class "Default")
      (node (ref "J14") (pin "10") (pinfunction "10_10") (pintype "passive"))
    )
    (net (code "139") (name "unconnected-(J14-Pad11)") (class "Default")
      (node (ref "J14") (pin "11") (pinfunction "11_11") (pintype "passive"))
    )
    (net (code "140") (name "unconnected-(J14-Pad12)") (class "Default")
      (node (ref "J14") (pin "12") (pinfunction "12_12") (pintype "passive"))
    )
    (net (code "141") (name "unconnected-(J14-Pad13)") (class "Default")
      (node (ref "J14") (pin "13") (pinfunction "13_13") (pintype "passive"))
    )
    (net (code "142") (name "unconnected-(J14-Pad14)") (class "Default")
      (node (ref "J14") (pin "14") (pinfunction "14_14") (pintype "passive"))
    )
    (net (code "143") (name "unconnected-(J14-Pad15)") (class "Default")
      (node (ref "J14") (pin "15") (pinfunction "15_15") (pintype "passive"))
    )
    (net (code "144") (name "unconnected-(J14-Pad16)") (class "Default")
      (node (ref "J14") (pin "16") (pinfunction "16_16") (pintype "passive"))
    )
    (net (code "145") (name "unconnected-(J15-Pad1)") (class "Default")
      (node (ref "J15") (pin "1") (pinfunction "1_1") (pintype "passive"))
    )
    (net (code "146") (name "unconnected-(J15-Pad2)") (class "Default")
      (node (ref "J15") (pin "2") (pinfunction "2_2") (pintype "passive"))
    )
    (net (code "147") (name "unconnected-(J15-Pad3)") (class "Default")
      (node (ref "J15") (pin "3") (pinfunction "3_3") (pintype "passive"))
    )
    (net (code "148") (name "unconnected-(J15-Pad4)") (class "Default")
      (node (ref "J15") (pin "4") (pinfunction "4_4") (pintype "passive"))
    )
    (net (code "149") (name "unconnected-(J15-Pad5)") (class "Default")
      (node (ref "J15") (pin "5") (pinfunction "5_5") (pintype "passive"))
    )
    (net (code "150") (name "unconnected-(J15-Pad6)") (class "Default")
      (node (ref "J15") (pin "6") (pinfunction "6_6") (pintype "passive"))
    )
    (net (code "151") (name "unconnected-(J15-Pad7)") (class "Default")
      (node (ref "J15") (pin "7") (pinfunction "7_7") (pintype "passive"))
    )
    (net (code "152") (name "unconnected-(J15-Pad8)") (class "Default")
      (node (ref "J15") (pin "8") (pinfunction "8_8") (pintype "passive"))
    )
    (net (code "153") (name "unconnected-(J15-Pad9)") (class "Default")
      (node (ref "J15") (pin "9") (pinfunction "9_9") (pintype "passive"))
    )
    (net (code "154") (name "unconnected-(J15-Pad10)") (class "Default")
      (node (ref "J15") (pin "10") (pinfunction "10_10") (pintype "passive"))
    )
    (net (code "155") (name "unconnected-(J15-Pad11)") (class "Default")
      (node (ref "J15") (pin "11") (pinfunction "11_11") (pintype "passive"))
    )
    (net (code "156") (name "unconnected-(J15-Pad12)") (class "Default")
      (node (ref "J15") (pin "12") (pinfunction "12_12") (pintype "passive"))
    )
    (net (code "157") (name "unconnected-(J15-Pad13)") (class "Default")
      (node (ref "J15") (pin "13") (pinfunction "13_13") (pintype "passive"))
    )
    (net (code "158") (name "unconnected-(J15-Pad14)") (class "Default")
      (node (ref "J15") (pin "14") (pinfunction "14_14") (pintype "passive"))
    )
    (net (code "159") (name "unconnected-(J15-Pad15)") (class "Default")
      (node (ref "J15") (pin "15") (pinfunction "15_15") (pintype "passive"))
    )
    (net (code "160") (name "unconnected-(J15-Pad16)") (class "Default")
      (node (ref "J15") (pin "16") (pinfunction "16_16") (pintype "passive"))
    )
    (net (code "161") (name "unconnected-(J16-Pad1)") (class "Default")
      (node (ref "J16") (pin "1") (pinfunction "1_1") (pintype "passive"))
    )
    (net (code "162") (name "unconnected-(J16-Pad2)") (class "Default")
      (node (ref "J16") (pin "2") (pinfunction "2_2") (pintype "passive"))
    )
    (net (code "163") (name "unconnected-(J16-Pad3)") (class "Default")
      (node (ref "J16") (pin "3") (pinfunction "3_3") (pintype "passive"))
    )
    (net (code "164") (name "unconnected-(J16-Pad4)") (class "Default")
      (node (ref "J16") (pin "4") (pinfunction "4_4") (pintype "passive"))
    )
    (net (code "165") (name "unconnected-(J16-Pad5)") (class "Default")
      (node (ref "J16") (pin "5") (pinfunction "5_5") (pintype "passive"))
    )
    (net (code "166") (name "unconnected-(J16-Pad6)") (class "Default")
      (node (ref "J16") (pin "6") (pinfunction "6_6") (pintype "passive"))
    )
    (net (code "167") (name "unconnected-(J16-Pad7)") (class "Default")
      (node (ref "J16") (pin "7") (pinfunction "7_7") (pintype "passive"))
    )
    (net (code "168") (name "unconnected-(J16-Pad8)") (class "Default")
      (node (ref "J16") (pin "8") (pinfunction "8_8") (pintype "passive"))
    )
    (net (code "169") (name "unconnected-(J16-Pad9)") (class "Default")
      (node (ref "J16") (pin "9") (pinfunction "9_9") (pintype "passive"))
    )
    (net (code "170") (name "unconnected-(J16-Pad10)") (class "Default")
      (node (ref "J16") (pin "10") (pinfunction "10_10") (pintype "passive"))
    )
    (net (code "171") (name "unconnected-(J16-Pad11)") (class "Default")
      (node (ref "J16") (pin "11") (pinfunction "11_11") (pintype "passive"))
    )
    (net (code "172") (name "unconnected-(J16-Pad12)") (class "Default")
      (node (ref "J16") (pin "12") (pinfunction "12_12") (pintype "passive"))
    )
    (net (code "173") (name "unconnected-(J16-Pad13)") (class "Default")
      (node (ref "J16") (pin "13") (pinfunction "13_13") (pintype "passive"))
    )
    (net (code "174") (name "unconnected-(J16-Pad14)") (class "Default")
      (node (ref "J16") (pin "14") (pinfunction "14_14") (pintype "passive"))
    )
    (net (code "175") (name "unconnected-(J16-Pad15)") (class "Default")
      (node (ref "J16") (pin "15") (pinfunction "15_15") (pintype "passive"))
    )
    (net (code "176") (name "unconnected-(J16-Pad16)") (class "Default")
      (node (ref "J16") (pin "16") (pinfunction "16_16") (pintype "passive"))
    )
    (net (code "177") (name "unconnected-(J17-Pad1)") (class "Default")
      (node (ref "J17") (pin "1") (pinfunction "1_1") (pintype "passive"))
    )
    (net (code "178") (name "unconnected-(J17-Pad2)") (class "Default")
      (node (ref "J17") (pin "2") (pinfunction "2_2") (pintype "passive"))
    )
    (net (code "179") (name "unconnected-(J17-Pad3)") (class "Default")
      (node (ref "J17") (pin "3") (pinfunction "3_3") (pintype "passive"))
    )
    (net (code "180") (name "unconnected-(J17-Pad4)") (class "Default")
      (node (ref "J17") (pin "4") (pinfunction "4_4") (pintype "passive"))
    )
    (net (code "181") (name "unconnected-(J17-Pad5)") (class "Default")
      (node (ref "J17") (pin "5") (pinfunction "5_5") (pintype "passive"))
    )
    (net (code "182") (name "unconnected-(J17-Pad6)") (class "Default")
      (node (ref "J17") (pin "6") (pinfunction "6_6") (pintype "passive"))
    )
    (net (code "183") (name "unconnected-(J17-Pad7)") (class "Default")
      (node (ref "J17") (pin "7") (pinfunction "7_7") (pintype "passive"))
    )
    (net (code "184") (name "unconnected-(J17-Pad8)") (class "Default")
      (node (ref "J17") (pin "8") (pinfunction "8_8") (pintype "passive"))
    )
    (net (code "185") (name "unconnected-(J17-Pad9)") (class "Default")
      (node (ref "J17") (pin "9") (pinfunction "9_9") (pintype "passive"))
    )
    (net (code "186") (name "unconnected-(J17-Pad10)") (class "Default")
      (node (ref "J17") (pin "10") (pinfunction "10_10") (pintype "passive"))
    )
    (net (code "187") (name "unconnected-(J17-Pad11)") (class "Default")
      (node (ref "J17") (pin "11") (pinfunction "11_11") (pintype "passive"))
    )
    (net (code "188") (name "unconnected-(J17-Pad12)") (class "Default")
      (node (ref "J17") (pin "12") (pinfunction "12_12") (pintype "passive"))
    )
    (net (code "189") (name "unconnected-(J17-Pad13)") (class "Default")
      (node (ref "J17") (pin "13") (pinfunction "13_13") (pintype "passive"))
    )
    (net (code "190") (name "unconnected-(J17-Pad14)") (class "Default")
      (node (ref "J17") (pin "14") (pinfunction "14_14") (pintype "passive"))
    )
    (net (code "191") (name "unconnected-(J17-Pad15)") (class "Default")
      (node (ref "J17") (pin "15") (pinfunction "15_15") (pintype "passive"))
    )
    (net (code "192") (name "unconnected-(J17-Pad16)") (class "Default")
      (node (ref "J17") (pin "16") (pinfunction "16_16") (pintype "passive"))
    )
    (net (code "193") (name "unconnected-(J18-Pad1)") (class "Default")
      (node (ref "J18") (pin "1") (pinfunction "1_1") (pintype "passive"))
    )
    (net (code "194") (name "unconnected-(J18-Pad2)") (class "Default")
      (node (ref "J18") (pin "2") (pinfunction "2_2") (pintype "passive"))
    )
    (net (code "195") (name "unconnected-(J18-Pad3)") (class "Default")
      (node (ref "J18") (pin "3") (pinfunction "3_3") (pintype "passive"))
    )
    (net (code "196") (name "unconnected-(J18-Pad4)") (class "Default")
      (node (ref "J18") (pin "4") (pinfunction "4_4") (pintype "passive"))
    )
    (net (code "197") (name "unconnected-(J18-Pad5)") (class "Default")
      (node (ref "J18") (pin "5") (pinfunction "5_5") (pintype "passive"))
    )
    (net (code "198") (name "unconnected-(J18-Pad6)") (class "Default")
      (node (ref "J18") (pin "6") (pinfunction "6_6") (pintype "passive"))
    )
    (net (code "199") (name "unconnected-(J18-Pad7)") (class "Default")
      (node (ref "J18") (pin "7") (pinfunction "7_7") (pintype "passive"))
    )
    (net (code "200") (name "unconnected-(J18-Pad8)") (class "Default")
      (node (ref "J18") (pin "8") (pinfunction "8_8") (pintype "passive"))
    )
    (net (code "201") (name "unconnected-(J18-Pad9)") (class "Default")
      (node (ref "J18") (pin "9") (pinfunction "9_9") (pintype "passive"))
    )
    (net (code "202") (name "unconnected-(J18-Pad10)") (class "Default")
      (node (ref "J18") (pin "10") (pinfunction "10_10") (pintype "passive"))
    )
    (net (code "203") (name "unconnected-(J18-Pad11)") (class "Default")
      (node (ref "J18") (pin "11") (pinfunction "11_11") (pintype "passive"))
    )
    (net (code "204") (name "unconnected-(J18-Pad12)") (class "Default")
      (node (ref "J18") (pin "12") (pinfunction "12_12") (pintype "passive"))
    )
    (net (code "205") (name "unconnected-(J18-Pad13)") (class "Default")
      (node (ref "J18") (pin "13") (pinfunction "13_13") (pintype "passive"))
    )
    (net (code "206") (name "unconnected-(J18-Pad14)") (class "Default")
      (node (ref "J18") (pin "14") (pinfunction "14_14") (pintype "passive"))
    )
    (net (code "207") (name "unconnected-(J18-Pad15)") (class "Default")
      (node (ref "J18") (pin "15") (pinfunction "15_15") (pintype "passive"))
    )
    (net (code "208") (name "unconnected-(J18-Pad16)") (class "Default")
      (node (ref "J18") (pin "16") (pinfunction "16_16") (pintype "passive"))
    )
    (net (code "209") (name "unconnected-(J19-Pad1)") (class "Default")
      (node (ref "J19") (pin "1") (pinfunction "1_1") (pintype "passive"))
    )
    (net (code "210") (name "unconnected-(J19-Pad2)") (class "Default")
      (node (ref "J19") (pin "2") (pinfunction "2_2") (pintype "passive"))
    )
    (net (code "211") (name "unconnected-(J19-Pad3)") (class "Default")
      (node (ref "J19") (pin "3") (pinfunction "3_3") (pintype "passive"))
    )
    (net (code "212") (name "unconnected-(J19-Pad4)") (class "Default")
      (node (ref "J19") (pin "4") (pinfunction "4_4") (pintype "passive"))
    )
    (net (code "213") (name "unconnected-(J19-Pad5)") (class "Default")
      (node (ref "J19") (pin "5") (pinfunction "5_5") (pintype "passive"))
    )
    (net (code "214") (name "unconnected-(J19-Pad6)") (class "Default")
      (node (ref "J19") (pin "6") (pinfunction "6_6") (pintype "passive"))
    )
    (net (code "215") (name "unconnected-(J19-Pad7)") (class "Default")
      (node (ref "J19") (pin "7") (pinfunction "7_7") (pintype "passive"))
    )
    (net (code "216") (name "unconnected-(J19-Pad8)") (class "Default")
      (node (ref "J19") (pin "8") (pinfunction "8_8") (pintype "passive"))
    )
    (net (code "217") (name "unconnected-(J19-Pad9)") (class "Default")
      (node (ref "J19") (pin "9") (pinfunction "9_9") (pintype "passive"))
    )
    (net (code "218") (name "unconnected-(J19-Pad10)") (class "Default")
      (node (ref "J19") (pin "10") (pinfunction "10_10") (pintype "passive"))
    )
    (net (code "219") (name "unconnected-(J19-Pad11)") (class "Default")
      (node (ref "J19") (pin "11") (pinfunction "11_11") (pintype "passive"))
    )
    (net (code "220") (name "unconnected-(J19-Pad12)") (class "Default")
      (node (ref "J19") (pin "12") (pinfunction "12_12") (pintype "passive"))
    )
    (net (code "221") (name "unconnected-(J19-Pad13)") (class "Default")
      (node (ref "J19") (pin "13") (pinfunction "13_13") (pintype "passive"))
    )
    (net (code "222") (name "unconnected-(J19-Pad14)") (class "Default")
      (node (ref "J19") (pin "14") (pinfunction "14_14") (pintype "passive"))
    )
    (net (code "223") (name "unconnected-(J19-Pad15)") (class "Default")
      (node (ref "J19") (pin "15") (pinfunction "15_15") (pintype "passive"))
    )
    (net (code "224") (name "unconnected-(J19-Pad16)") (class "Default")
      (node (ref "J19") (pin "16") (pinfunction "16_16") (pintype "passive"))
    )
    (net (code "225") (name "unconnected-(J20-Pad1)") (class "Default")
      (node (ref "J20") (pin "1") (pinfunction "1_1") (pintype "passive"))
    )
    (net (code "226") (name "unconnected-(J20-Pad2)") (class "Default")
      (node (ref "J20") (pin "2") (pinfunction "2_2") (pintype "passive"))
    )
    (net (code "227") (name "unconnected-(J20-Pad3)") (class "Default")
      (node (ref "J20") (pin "3") (pinfunction "3_3") (pintype "passive"))
    )
    (net (code "228") (name "unconnected-(J20-Pad4)") (class "Default")
      (node (ref "J20") (pin "4") (pinfunction "4_4") (pintype "passive"))
    )
    (net (code "229") (name "unconnected-(J20-Pad5)") (class "Default")
      (node (ref "J20") (pin "5") (pinfunction "5_5") (pintype "passive"))
    )
    (net (code "230") (name "unconnected-(J20-Pad6)") (class "Default")
      (node (ref "J20") (pin "6") (pinfunction "6_6") (pintype "passive"))
    )
    (net (code "231") (name "unconnected-(J20-Pad7)") (class "Default")
      (node (ref "J20") (pin "7") (pinfunction "7_7") (pintype "passive"))
    )
    (net (code "232") (name "unconnected-(J20-Pad8)") (class "Default")
      (node (ref "J20") (pin "8") (pinfunction "8_8") (pintype "passive"))
    )
    (net (code "233") (name "unconnected-(J20-Pad9)") (class "Default")
      (node (ref "J20") (pin "9") (pinfunction "9_9") (pintype "passive"))
    )
    (net (code "234") (name "unconnected-(J20-Pad10)") (class "Default")
      (node (ref "J20") (pin "10") (pinfunction "10_10") (pintype "passive"))
    )
    (net (code "235") (name "unconnected-(J20-Pad11)") (class "Default")
      (node (ref "J20") (pin "11") (pinfunction "11_11") (pintype "passive"))
    )
    (net (code "236") (name "unconnected-(J20-Pad12)") (class "Default")
      (node (ref "J20") (pin "12") (pinfunction "12_12") (pintype "passive"))
    )
    (net (code "237") (name "unconnected-(J20-Pad13)") (class "Default")
      (node (ref "J20") (pin "13") (pinfunction "13_13") (pintype "passive"))
    )
    (net (code "238") (name "unconnected-(J20-Pad14)") (class "Default")
      (node (ref "J20") (pin "14") (pinfunction "14_14") (pintype "passive"))
    )
    (net (code "239") (name "unconnected-(J20-Pad15)") (class "Default")
      (node (ref "J20") (pin "15") (pinfunction "15_15") (pintype "passive"))
    )
    (net (code "240") (name "unconnected-(J20-Pad16)") (class "Default")
      (node (ref "J20") (pin "16") (pinfunction "16_16") (pintype "passive"))
    )
    (net (code "241") (name "unconnected-(J21-Pad1)") (class "Default")
      (node (ref "J21") (pin "1") (pinfunction "1_1") (pintype "passive"))
    )
    (net (code "242") (name "unconnected-(J21-Pad2)") (class "Default")
      (node (ref "J21") (pin "2") (pinfunction "2_2") (pintype "passive"))
    )
    (net (code "243") (name "unconnected-(J21-Pad3)") (class "Default")
      (node (ref "J21") (pin "3") (pinfunction "3_3") (pintype "passive"))
    )
    (net (code "244") (name "unconnected-(J21-Pad4)") (class "Default")
      (node (ref "J21") (pin "4") (pinfunction "4_4") (pintype "passive"))
    )
    (net (code "245") (name "unconnected-(J22-Pad1)") (class "Default")
      (node (ref "J22") (pin "1") (pinfunction "1_1") (pintype "passive"))
    )
    (net (code "246") (name "unconnected-(J22-Pad2)") (class "Default")
      (node (ref "J22") (pin "2") (pinfunction "2_2") (pintype "passive"))
    )
    (net (code "247") (name "unconnected-(J22-Pad3)") (class "Default")
      (node (ref "J22") (pin "3") (pinfunction "3_3") (pintype "passive"))
    )
    (net (code "248") (name "unconnected-(J22-Pad4)") (class "Default")
      (node (ref "J22") (pin "4") (pinfunction "4_4") (pintype "passive"))
    )
    (net (code "249") (name "unconnected-(J28-Pad1)") (class "Default")
      (node (ref "J28") (pin "1") (pinfunction "1_1") (pintype "passive"))
    )
    (net (code "250") (name "unconnected-(J28-Pad2)") (class "Default")
      (node (ref "J28") (pin "2") (pinfunction "2_2") (pintype "passive"))
    )
    (net (code "251") (name "unconnected-(J28-Pad3)") (class "Default")
      (node (ref "J28") (pin "3") (pinfunction "3_3") (pintype "passive"))
    )
    (net (code "252") (name "unconnected-(J28-Pad4)") (class "Default")
      (node (ref "J28") (pin "4") (pinfunction "4_4") (pintype "passive"))
    )
  )
)
